# LightSensitiveDCPower.net
KiCad netlist of a schematic drawn in EAGLE
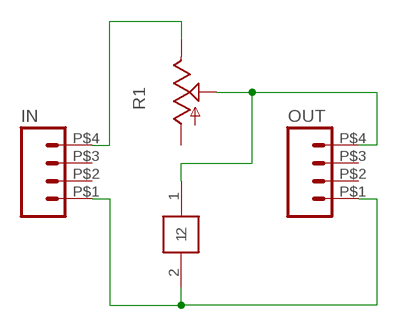
[diagram p0: schematic, sheet 1]

(export (version "E")
  (design (tool "Eeschema 10.0.6"))
  (components
    (comp (ref "IN")
      (value "M04HORIZ_PTH")
      (footprint "eagle-import:SULLIN-1X4_HORIZ")
      (libsource (lib "eagle-import") (part "M04HORIZ_PTH"))
    )
    (comp (ref "OUT")
      (value "M04HORIZ_PTH")
      (footprint "eagle-import:SULLIN-1X4_HORIZ")
      (libsource (lib "eagle-import") (part "M04HORIZ_PTH"))
    )
    (comp (ref "PC1")
      (value "PDV-P8101")
      (footprint "eagle-import:PHOTOCELL_CERAMIC")
      (libsource (lib "eagle-import") (part "PDV-P8101"))
    )
    (comp (ref "R1")
      (value "TRIM_US-B25P")
      (footprint "eagle-import:B25P")
      (libsource (lib "eagle-import") (part "TRIM_US-B25P"))
    )
  )
  (nets
    (net (code "1") (name "Net-(IN-1)") (class "Default")
      (node (ref "IN") (pin "P$1") (pinfunction "1_P$1") (pintype "passive"))
      (node (ref "OUT") (pin "P$1") (pinfunction "1_P$1") (pintype "passive"))
      (node (ref "PC1") (pin "2") (pinfunction "2_2") (pintype "bidirectional"))
    )
    (net (code "2") (name "Net-(IN-4)") (class "Default")
      (node (ref "IN") (pin "P$4") (pinfunction "4_P$4") (pintype "passive"))
      (node (ref "R1") (pin "E") (pinfunction "E_E") (pintype "passive"))
    )
    (net (code "3") (name "Net-(OUT-4)") (class "Default")
      (node (ref "OUT") (pin "P$4") (pinfunction "4_P$4") (pintype "passive"))
      (node (ref "PC1") (pin "1") (pinfunction "1_1") (pintype "bidirectional"))
      (node (ref "R1") (pin "S") (pinfunction "S_S") (pintype "passive"))
    )
    (net (code "4") (name "unconnected-(IN-2-PadP$2)") (class "Default")
      (node (ref "IN") (pin "P$2") (pinfunction "2_P$2") (pintype "passive"))
    )
    (net (code "5") (name "unconnected-(IN-3-PadP$3)") (class "Default")
      (node (ref "IN") (pin "P$3") (pinfunction "3_P$3") (pintype "passive"))
    )
    (net (code "6") (name "unconnected-(OUT-2-PadP$2)") (class "Default")
      (node (ref "OUT") (pin "P$2") (pinfunction "2_P$2") (pintype "passive"))
    )
    (net (code "7") (name "unconnected-(OUT-3-PadP$3)") (class "Default")
      (node (ref "OUT") (pin "P$3") (pinfunction "3_P$3") (pintype "passive"))
    )
    (net (code "8") (name "unconnected-(R1-PadA)") (class "Default")
      (node (ref "R1") (pin "A") (pinfunction "A_A") (pintype "passive"))
    )
  )
)
